# 300_MCU.net
KiCad netlist of a schematic drawn in Altium Designer
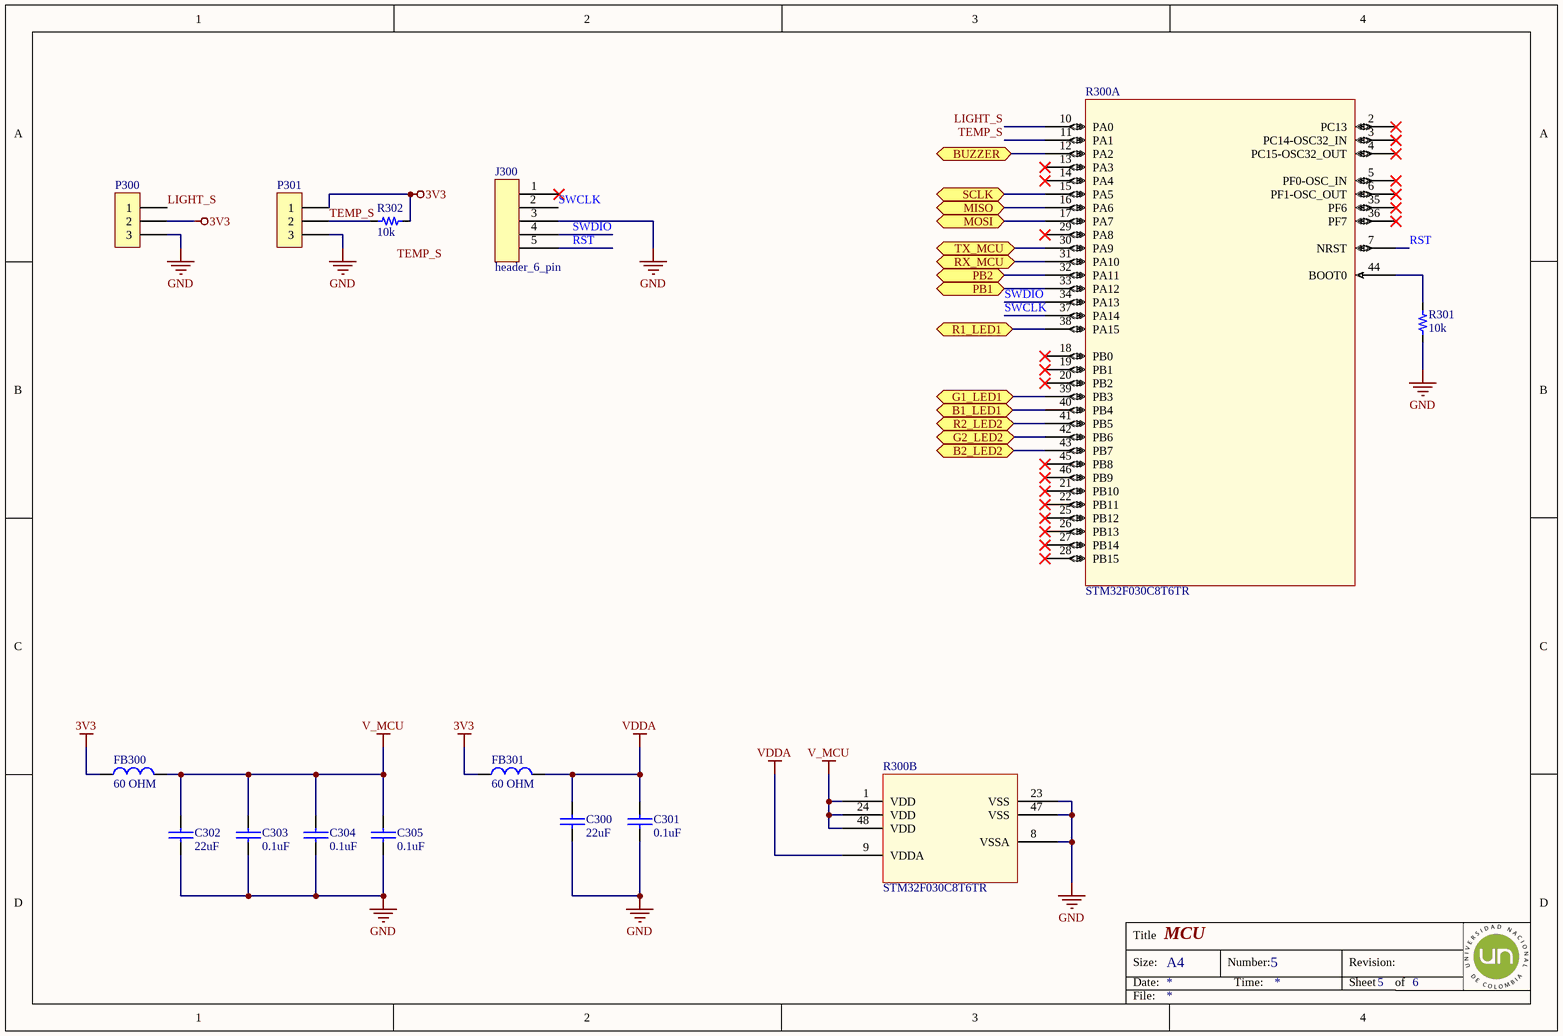
[diagram p0: 300_MCU.SchDoc]

(export (version "E")
  (design (tool "Eeschema 10.0.6"))
  (components
    (comp (ref "C300")
      (value "22uF")
      (footprint "0603_cap")
      (description "6.3V 22uF X5R ±20% 0805 Multilayer Ceramic Capacitors MLCC - SMD/SMT ROHS")
      (fields
        (field (name "MANUFACTURER") "Samsung Electro-Mechanics")
        (field (name "MANUFACTURER PART NUMBER") "CL21A226MQQNNNE")
      )
      (libsource (lib "shared_lib") (part "Cap_22uF_0805_6V3"))
    )
    (comp (ref "C301")
      (value "0.1uF")
      (footprint "0603_cap")
      (description "50V 100nF Y5V -20%~+80% 0603 Multilayer Ceramic Capacitors MLCC - SMD/SMT ROHS")
      (fields
        (field (name "MANUFACTURER") "Walsin Tech Corp")
        (field (name "MANUFACTURER PART NUMBER") "0603F104Z500CT")
      )
      (libsource (lib "shared_lib") (part "Cap_0.1uF_0603_50V"))
    )
    (comp (ref "C302")
      (value "22uF")
      (footprint "0603_cap")
      (description "6.3V 22uF X5R ±20% 0805 Multilayer Ceramic Capacitors MLCC - SMD/SMT ROHS")
      (fields
        (field (name "MANUFACTURER") "Samsung Electro-Mechanics")
        (field (name "MANUFACTURER PART NUMBER") "CL21A226MQQNNNE")
      )
      (libsource (lib "shared_lib") (part "Cap_22uF_0805_6V3"))
    )
    (comp (ref "C303")
      (value "0.1uF")
      (footprint "0603_cap")
      (description "50V 100nF Y5V -20%~+80% 0603 Multilayer Ceramic Capacitors MLCC - SMD/SMT ROHS")
      (fields
        (field (name "MANUFACTURER") "Walsin Tech Corp")
        (field (name "MANUFACTURER PART NUMBER") "0603F104Z500CT")
      )
      (libsource (lib "shared_lib") (part "Cap_0.1uF_0603_50V"))
    )
    (comp (ref "C304")
      (value "0.1uF")
      (footprint "0603_cap")
      (description "50V 100nF Y5V -20%~+80% 0603 Multilayer Ceramic Capacitors MLCC - SMD/SMT ROHS")
      (fields
        (field (name "MANUFACTURER") "Walsin Tech Corp")
        (field (name "MANUFACTURER PART NUMBER") "0603F104Z500CT")
      )
      (libsource (lib "shared_lib") (part "Cap_0.1uF_0603_50V"))
    )
    (comp (ref "C305")
      (value "0.1uF")
      (footprint "0603_cap")
      (description "50V 100nF Y5V -20%~+80% 0603 Multilayer Ceramic Capacitors MLCC - SMD/SMT ROHS")
      (fields
        (field (name "MANUFACTURER") "Walsin Tech Corp")
        (field (name "MANUFACTURER PART NUMBER") "0603F104Z500CT")
      )
      (libsource (lib "shared_lib") (part "Cap_0.1uF_0603_50V"))
    )
    (comp (ref "FB300")
      (value "60 OHM")
      (footprint "0603_fb")
      (description "2A 1 100mΩ 60Ω@100MHz ±25% 0603 Ferrite Beads ROHS")
      (fields
        (field (name "MANUFACTURER") "TAI-TECH")
        (field (name "MANUFACTURER PART NUMBER") "HCB1608KF-600T20")
      )
      (libsource (lib "shared_lib") (part "FB_60_0603_2A"))
    )
    (comp (ref "FB301")
      (value "60 OHM")
      (footprint "0603_fb")
      (description "2A 1 100mΩ 60Ω@100MHz ±25% 0603 Ferrite Beads ROHS")
      (fields
        (field (name "MANUFACTURER") "TAI-TECH")
        (field (name "MANUFACTURER PART NUMBER") "HCB1608KF-600T20")
      )
      (libsource (lib "shared_lib") (part "FB_60_0603_2A"))
    )
    (comp (ref "J300")
      (value "header_6_pin")
      (footprint "header_6_pin")
      (fields (field (name "MANUFACTURER") "XFCN") (field (name "MANUFACTURER PART NUMBER") "PZ200V-11-05P"))
      (libsource (lib "lib_proj_6") (part "header_6_pin"))
    )
    (comp (ref "P300")
      (value "HEAD_FEMALE_3")
      (footprint "HEAD_FEMALE_3")
      (description "2.54mm 单排 Gold Straight 1x3P 3 Plugin,P=2.54mm Female Headers ROHS")
      (fields (field (name "MANUFACTURE PART NUMBER") "MTF185-103SY1"))
      (libsource (lib "lib_proj_6") (part "HEAD_FEMALE_3"))
    )
    (comp (ref "P301")
      (value "HEAD_FEMALE_3")
      (footprint "HEAD_FEMALE_3")
      (description "2.54mm 单排 Gold Straight 1x3P 3 Plugin,P=2.54mm Female Headers ROHS")
      (fields (field (name "MANUFACTURE PART NUMBER") "MTF185-103SY1"))
      (libsource (lib "lib_proj_6") (part "HEAD_FEMALE_3"))
    )
    (comp (ref "R300")
      (value "STM32F030C8T6TR")
      (footprint "LQFP48_7x7mm")
      (description "IC MCU 32BIT 64KB FLASH 48LQFP")
      (fields (field (name "MANUFACTURER") "STMicroelectronics"))
      (libsource (lib "") (part "IC_STM32F030C8T6TR_LQFP48_7x7MM_1"))
    )
    (comp (ref "R301")
      (value "10k")
      (footprint "0603_res")
      (description "RES SMD 10k OHM 5% 1/10W 0603")
      (fields (field (name "MANUFACTURER") "FOJAN") (field (name "MANUFACTURER PART NUMBER") "FRC0603J103TS"))
      (libsource (lib "shared_lib") (part "Res_10k_0603_1/10W"))
    )
    (comp (ref "R302")
      (value "10k")
      (footprint "0603_res")
      (description "RES SMD 10k OHM 5% 1/10W 0603")
      (fields (field (name "MANUFACTURER") "FOJAN") (field (name "MANUFACTURER PART NUMBER") "FRC0603J103TS"))
      (libsource (lib "shared_lib") (part "Res_10k_0603_1/10W"))
    )
  )
  (nets
    (net (code "1") (name "/B1_LED1") (class "Default")
      (node (ref "R300") (pin "40") (pinfunction "PB4_40") (pintype "bidirectional"))
    )
    (net (code "2") (name "/B2_LED2") (class "Default")
      (node (ref "R300") (pin "43") (pinfunction "PB7_43") (pintype "bidirectional"))
    )
    (net (code "3") (name "/BUZZER") (class "Default")
      (node (ref "R300") (pin "12") (pinfunction "PA2_12") (pintype "bidirectional"))
    )
    (net (code "4") (name "/G1_LED1") (class "Default")
      (node (ref "R300") (pin "39") (pinfunction "PB3_39") (pintype "bidirectional"))
    )
    (net (code "5") (name "/G2_LED2") (class "Default")
      (node (ref "R300") (pin "42") (pinfunction "PB6_42") (pintype "bidirectional"))
    )
    (net (code "6") (name "/LIGHT_S") (class "Default")
      (node (ref "P300") (pin "1") (pinfunction "1_1") (pintype "passive"))
      (node (ref "R300") (pin "10") (pinfunction "PA0_10") (pintype "bidirectional"))
    )
    (net (code "7") (name "/MISO") (class "Default")
      (node (ref "R300") (pin "16") (pinfunction "PA6_16") (pintype "bidirectional"))
    )
    (net (code "8") (name "/MOSI") (class "Default")
      (node (ref "R300") (pin "17") (pinfunction "PA7_17") (pintype "bidirectional"))
    )
    (net (code "9") (name "/PB1") (class "Default")
      (node (ref "R300") (pin "33") (pinfunction "PA12_33") (pintype "bidirectional"))
    )
    (net (code "10") (name "/PB2") (class "Default")
      (node (ref "R300") (pin "32") (pinfunction "PA11_32") (pintype "bidirectional"))
    )
    (net (code "11") (name "/R1_LED1") (class "Default")
      (node (ref "R300") (pin "38") (pinfunction "PA15_38") (pintype "bidirectional"))
    )
    (net (code "12") (name "/R2_LED2") (class "Default")
      (node (ref "R300") (pin "41") (pinfunction "PB5_41") (pintype "bidirectional"))
    )
    (net (code "13") (name "/RST") (class "Default")
      (node (ref "J300") (pin "5") (pinfunction "9_5") (pintype "passive"))
      (node (ref "R300") (pin "7") (pinfunction "NRST_7") (pintype "bidirectional"))
    )
    (net (code "14") (name "/RX_MCU") (class "Default")
      (node (ref "R300") (pin "31") (pinfunction "PA10_31") (pintype "bidirectional"))
    )
    (net (code "15") (name "/SCLK") (class "Default")
      (node (ref "R300") (pin "15") (pinfunction "PA5_15") (pintype "bidirectional"))
    )
    (net (code "16") (name "/SWCLK") (class "Default")
      (node (ref "J300") (pin "2") (pinfunction "6_2") (pintype "passive"))
      (node (ref "R300") (pin "37") (pinfunction "PA14_37") (pintype "bidirectional"))
    )
    (net (code "17") (name "/SWDIO") (class "Default")
      (node (ref "J300") (pin "4") (pinfunction "8_4") (pintype "passive"))
      (node (ref "R300") (pin "34") (pinfunction "PA13_34") (pintype "bidirectional"))
    )
    (net (code "18") (name "/TEMP_S") (class "Default")
      (node (ref "P301") (pin "2") (pinfunction "2_2") (pintype "passive"))
      (node (ref "R300") (pin "11") (pinfunction "PA1_11") (pintype "bidirectional"))
      (node (ref "R302") (pin "1") (pinfunction "1_1") (pintype "passive"))
    )
    (net (code "19") (name "/TX_MCU") (class "Default")
      (node (ref "R300") (pin "30") (pinfunction "PA9_30") (pintype "bidirectional"))
    )
    (net (code "20") (name "3V3") (class "Default")
      (node (ref "FB300") (pin "1") (pinfunction "1_1") (pintype "passive"))
      (node (ref "FB301") (pin "1") (pinfunction "1_1") (pintype "passive"))
      (node (ref "P300") (pin "2") (pinfunction "2_2") (pintype "passive"))
      (node (ref "P301") (pin "1") (pinfunction "1_1") (pintype "passive"))
      (node (ref "R302") (pin "2") (pinfunction "2_2") (pintype "passive"))
    )
    (net (code "21") (name "GND") (class "Default")
      (node (ref "C300") (pin "2") (pinfunction "2_2") (pintype "passive"))
      (node (ref "C301") (pin "2") (pinfunction "2_2") (pintype "passive"))
      (node (ref "C302") (pin "2") (pinfunction "2_2") (pintype "passive"))
      (node (ref "C303") (pin "2") (pinfunction "2_2") (pintype "passive"))
      (node (ref "C304") (pin "2") (pinfunction "2_2") (pintype "passive"))
      (node (ref "C305") (pin "2") (pinfunction "2_2") (pintype "passive"))
      (node (ref "J300") (pin "3") (pinfunction "7_3") (pintype "passive"))
      (node (ref "P300") (pin "3") (pinfunction "3_3") (pintype "passive"))
      (node (ref "P301") (pin "3") (pinfunction "3_3") (pintype "passive"))
      (node (ref "R300") (pin "23") (pinfunction "VSS_23") (pintype "power_in"))
      (node (ref "R300") (pin "47") (pinfunction "VSS_47") (pintype "power_in"))
      (node (ref "R300") (pin "8") (pinfunction "VSSA_8") (pintype "power_in"))
      (node (ref "R301") (pin "1") (pinfunction "1_1") (pintype "passive"))
    )
    (net (code "22") (name "Net-(R300A-BOOT0)") (class "Default")
      (node (ref "R300") (pin "44") (pinfunction "BOOT0_44") (pintype "input"))
      (node (ref "R301") (pin "2") (pinfunction "2_2") (pintype "passive"))
    )
    (net (code "23") (name "VDDA") (class "Default")
      (node (ref "C300") (pin "1") (pinfunction "1_1") (pintype "passive"))
      (node (ref "C301") (pin "1") (pinfunction "1_1") (pintype "passive"))
      (node (ref "FB301") (pin "2") (pinfunction "2_2") (pintype "passive"))
      (node (ref "R300") (pin "9") (pinfunction "VDDA_9") (pintype "power_in"))
    )
    (net (code "24") (name "V_MCU") (class "Default")
      (node (ref "C302") (pin "1") (pinfunction "1_1") (pintype "passive"))
      (node (ref "C303") (pin "1") (pinfunction "1_1") (pintype "passive"))
      (node (ref "C304") (pin "1") (pinfunction "1_1") (pintype "passive"))
      (node (ref "C305") (pin "1") (pinfunction "1_1") (pintype "passive"))
      (node (ref "FB300") (pin "2") (pinfunction "2_2") (pintype "passive"))
      (node (ref "R300") (pin "1") (pinfunction "VDD_1") (pintype "power_in"))
      (node (ref "R300") (pin "24") (pinfunction "VDD_24") (pintype "power_in"))
      (node (ref "R300") (pin "48") (pinfunction "VDD_48") (pintype "power_in"))
    )
    (net (code "25") (name "unconnected-(J300-5-Pad1)") (class "Default")
      (node (ref "J300") (pin "1") (pinfunction "5_1") (pintype "passive+no_connect"))
    )
    (net (code "26") (name "unconnected-(R300A-PA3-Pad13)") (class "Default")
      (node (ref "R300") (pin "13") (pinfunction "PA3_13") (pintype "bidirectional+no_connect"))
    )
    (net (code "27") (name "unconnected-(R300A-PA4-Pad14)") (class "Default")
      (node (ref "R300") (pin "14") (pinfunction "PA4_14") (pintype "bidirectional+no_connect"))
    )
    (net (code "28") (name "unconnected-(R300A-PA8-Pad29)") (class "Default")
      (node (ref "R300") (pin "29") (pinfunction "PA8_29") (pintype "bidirectional+no_connect"))
    )
    (net (code "29") (name "unconnected-(R300A-PB0-Pad18)") (class "Default")
      (node (ref "R300") (pin "18") (pinfunction "PB0_18") (pintype "bidirectional+no_connect"))
    )
    (net (code "30") (name "unconnected-(R300A-PB1-Pad19)") (class "Default")
      (node (ref "R300") (pin "19") (pinfunction "PB1_19") (pintype "bidirectional+no_connect"))
    )
    (net (code "31") (name "unconnected-(R300A-PB2-Pad20)") (class "Default")
      (node (ref "R300") (pin "20") (pinfunction "PB2_20") (pintype "bidirectional+no_connect"))
    )
    (net (code "32") (name "unconnected-(R300A-PB8-Pad45)") (class "Default")
      (node (ref "R300") (pin "45") (pinfunction "PB8_45") (pintype "bidirectional+no_connect"))
    )
    (net (code "33") (name "unconnected-(R300A-PB9-Pad46)") (class "Default")
      (node (ref "R300") (pin "46") (pinfunction "PB9_46") (pintype "bidirectional+no_connect"))
    )
    (net (code "34") (name "unconnected-(R300A-PB10-Pad21)") (class "Default")
      (node (ref "R300") (pin "21") (pinfunction "PB10_21") (pintype "bidirectional+no_connect"))
    )
    (net (code "35") (name "unconnected-(R300A-PB11-Pad22)") (class "Default")
      (node (ref "R300") (pin "22") (pinfunction "PB11_22") (pintype "bidirectional+no_connect"))
    )
    (net (code "36") (name "unconnected-(R300A-PB12-Pad25)") (class "Default")
      (node (ref "R300") (pin "25") (pinfunction "PB12_25") (pintype "bidirectional+no_connect"))
    )
    (net (code "37") (name "unconnected-(R300A-PB13-Pad26)") (class "Default")
      (node (ref "R300") (pin "26") (pinfunction "PB13_26") (pintype "bidirectional+no_connect"))
    )
    (net (code "38") (name "unconnected-(R300A-PB14-Pad27)") (class "Default")
      (node (ref "R300") (pin "27") (pinfunction "PB14_27") (pintype "bidirectional+no_connect"))
    )
    (net (code "39") (name "unconnected-(R300A-PB15-Pad28)") (class "Default")
      (node (ref "R300") (pin "28") (pinfunction "PB15_28") (pintype "bidirectional+no_connect"))
    )
    (net (code "40") (name "unconnected-(R300A-PC13-Pad2)") (class "Default")
      (node (ref "R300") (pin "2") (pinfunction "PC13_2") (pintype "bidirectional+no_connect"))
    )
    (net (code "41") (name "unconnected-(R300A-PC14-OSC32_IN-Pad3)") (class "Default")
      (node (ref "R300") (pin "3") (pinfunction "PC14-OSC32_IN_3") (pintype "bidirectional+no_connect"))
    )
    (net (code "42") (name "unconnected-(R300A-PC15-OSC32_OUT-Pad4)") (class "Default")
      (node (ref "R300") (pin "4") (pinfunction "PC15-OSC32_OUT_4") (pintype "bidirectional+no_connect"))
    )
    (net (code "43") (name "unconnected-(R300A-PF0-OSC_IN-Pad5)") (class "Default")
      (node (ref "R300") (pin "5") (pinfunction "PF0-OSC_IN_5") (pintype "bidirectional+no_connect"))
    )
    (net (code "44") (name "unconnected-(R300A-PF1-OSC_OUT-Pad6)") (class "Default")
      (node (ref "R300") (pin "6") (pinfunction "PF1-OSC_OUT_6") (pintype "bidirectional+no_connect"))
    )
    (net (code "45") (name "unconnected-(R300A-PF6-Pad35)") (class "Default")
      (node (ref "R300") (pin "35") (pinfunction "PF6_35") (pintype "bidirectional+no_connect"))
    )
    (net (code "46") (name "unconnected-(R300A-PF7-Pad36)") (class "Default")
      (node (ref "R300") (pin "36") (pinfunction "PF7_36") (pintype "bidirectional+no_connect"))
    )
  )
)
